# CH32X305RCT-R0.net
KiCad netlist of a schematic drawn in Altium Designer
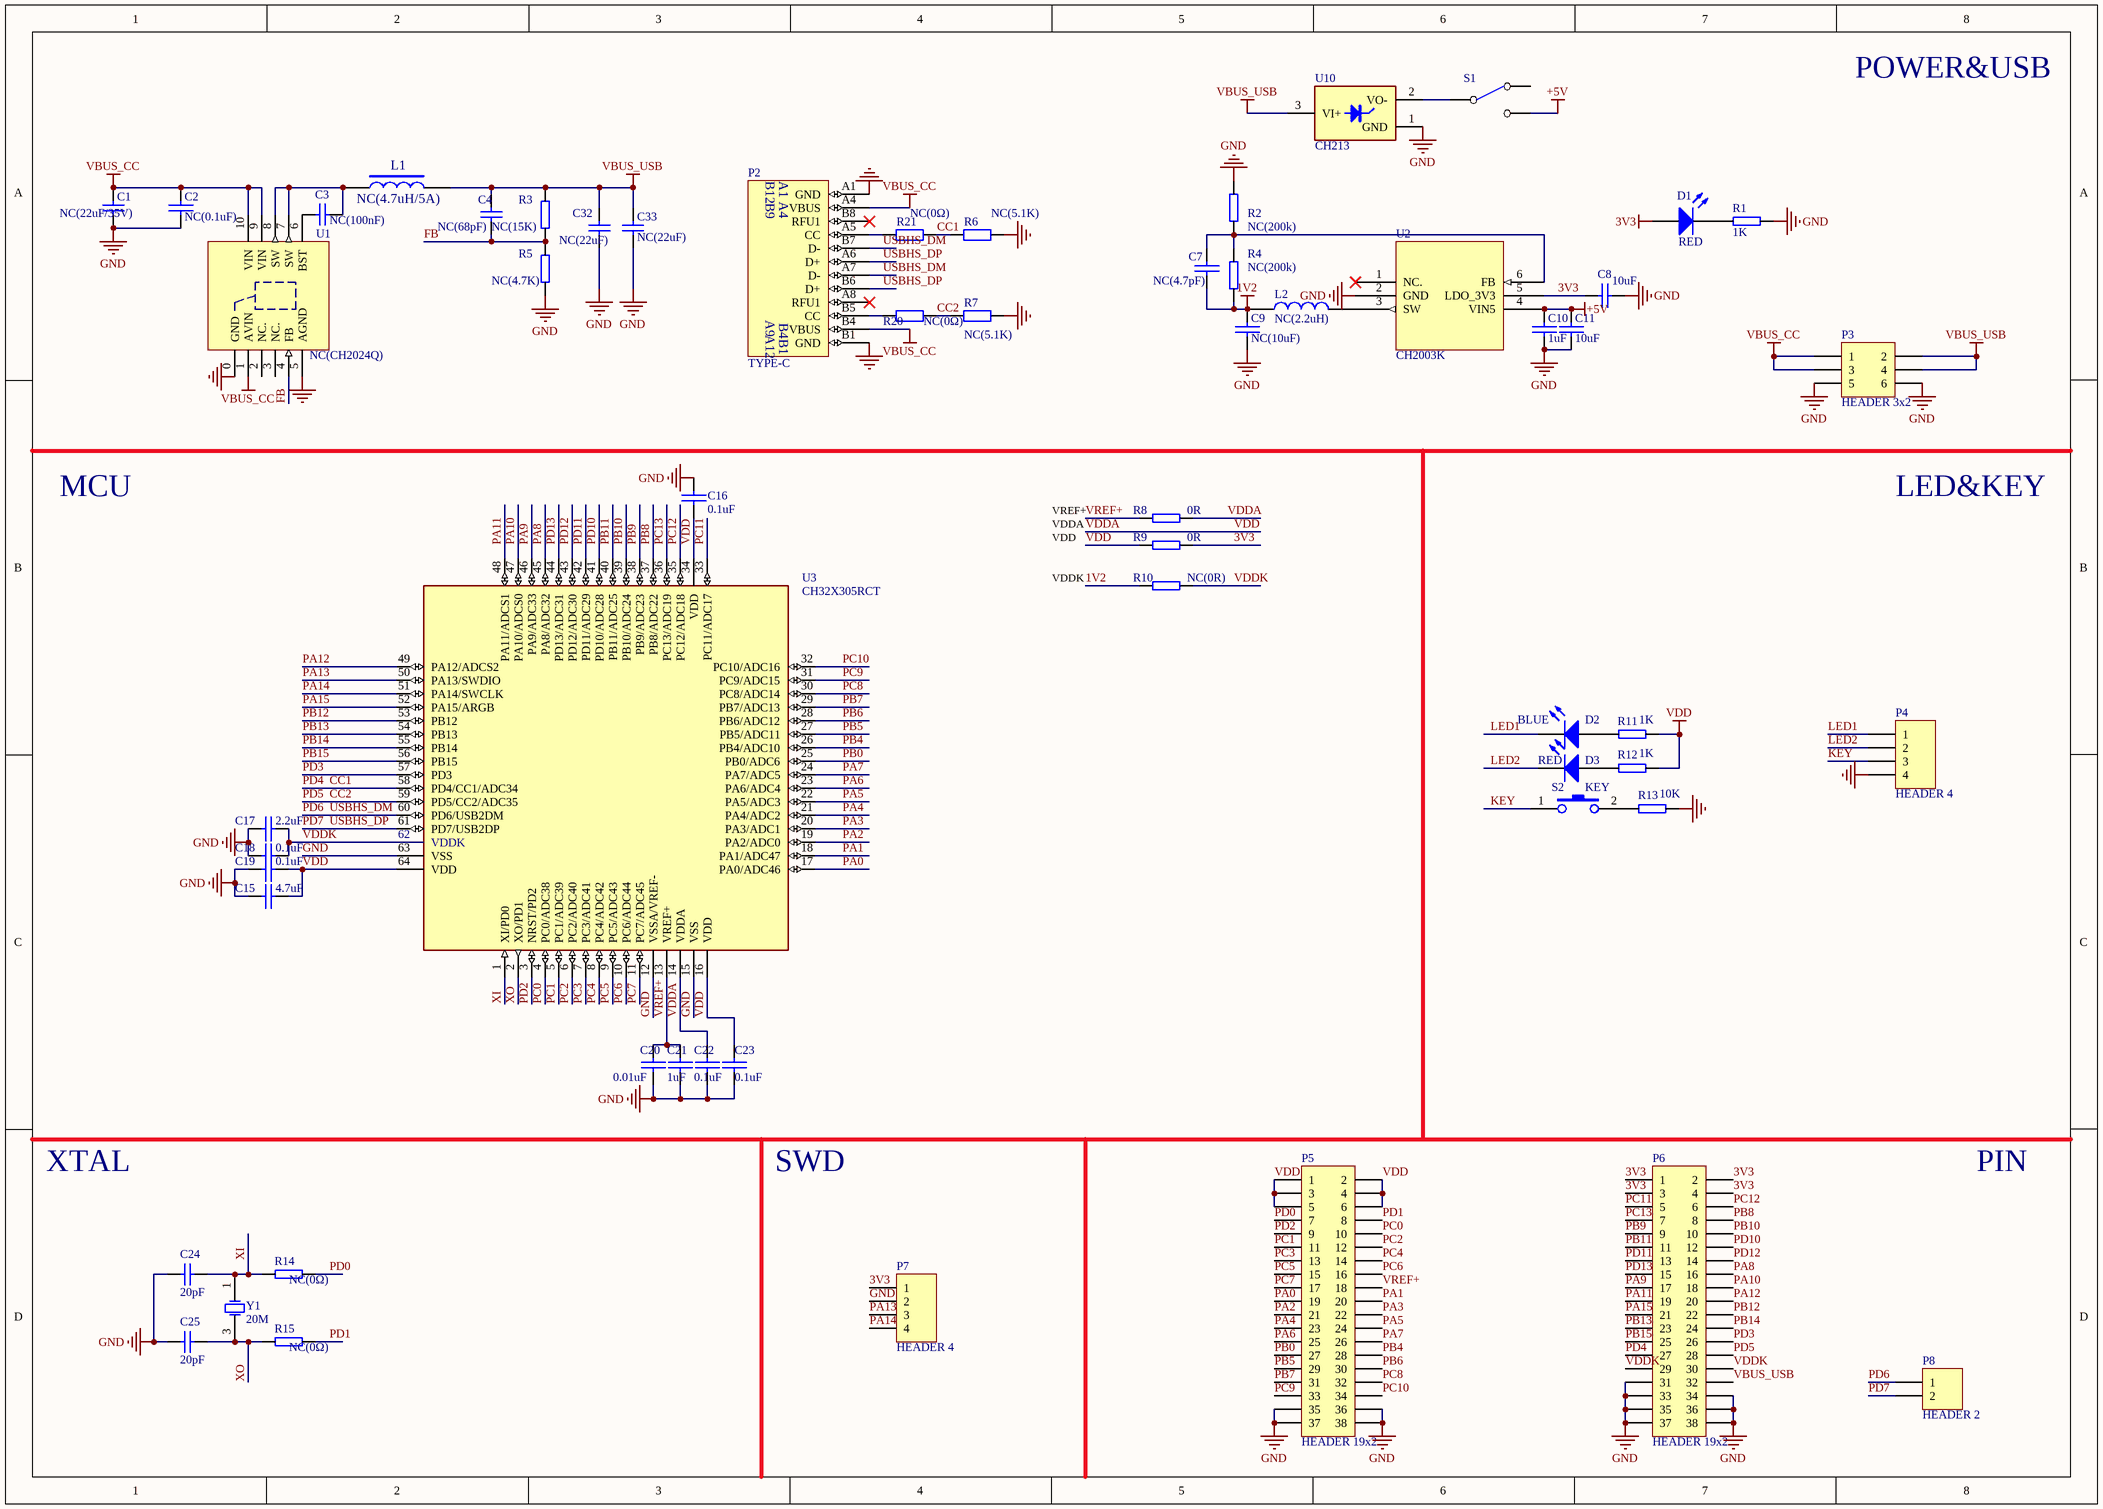
[diagram p0: CH32X305RCT-R0.SchDoc]

(export (version "E")
  (design (tool "Eeschema 10.0.6"))
  (components
    (comp (ref "C1")
      (value "NC(22uF/35V)")
      (footprint "0805_C")
      (description "贴片电容")
      (libsource (lib "Miscellaneous Devices LC") (part "0603 100nF (104) 10% 50V"))
    )
    (comp (ref "C2")
      (value "NC(0.1uF)")
      (footprint "0402_C")
      (description "Capacitor")
      (libsource (lib "") (part "CAP_1"))
    )
    (comp (ref "C3")
      (value "NC(100nF)")
      (footprint "0402_C")
      (description "贴片电容")
      (libsource (lib "Miscellaneous Devices LC") (part "0603 1uF (105) 10% 50V"))
    )
    (comp (ref "C4")
      (value "NC(68pF)")
      (footprint "0402_C")
      (description "贴片电容")
      (libsource (lib "Miscellaneous Devices LC") (part "0603 100nF (104) 10% 50V"))
    )
    (comp (ref "C7")
      (value "NC(4.7pF)")
      (footprint "0402_C")
      (description "Capacitor")
      (libsource (lib "*") (part "CAP"))
    )
    (comp (ref "C8")
      (value "10uF")
      (footprint "0603_C")
      (description "Capacitor")
      (libsource (lib "") (part "CAP_1"))
    )
    (comp (ref "C9")
      (value "NC(10uF)")
      (footprint "0603_C")
      (description "Capacitor")
      (libsource (lib "") (part "CAP_1"))
    )
    (comp (ref "C10")
      (value "1uF")
      (footprint "0402_C")
      (description "Capacitor")
      (libsource (lib "*") (part "CAP"))
    )
    (comp (ref "C11")
      (value "10uF")
      (footprint "0603_C")
      (description "Capacitor")
      (libsource (lib "") (part "CAP_1"))
    )
    (comp (ref "C15")
      (value "4.7uF")
      (footprint "0402_C")
      (description "Capacitor")
      (libsource (lib "*") (part "CAP"))
    )
    (comp (ref "C16")
      (value "0.1uF")
      (footprint "0402_C")
      (description "Capacitor")
      (libsource (lib "*") (part "CAP"))
    )
    (comp (ref "C17")
      (value "2.2uF")
      (footprint "0402_C")
      (description "Capacitor")
      (libsource (lib "*") (part "CAP"))
    )
    (comp (ref "C18")
      (value "0.1uF")
      (footprint "0402_C")
      (description "Capacitor")
      (libsource (lib "*") (part "CAP"))
    )
    (comp (ref "C19")
      (value "0.1uF")
      (footprint "0402_C")
      (description "Capacitor")
      (libsource (lib "*") (part "CAP"))
    )
    (comp (ref "C20")
      (value "0.01uF")
      (footprint "0402_C")
      (description "Capacitor")
      (libsource (lib "*") (part "CAP"))
    )
    (comp (ref "C21")
      (value "1uF")
      (footprint "0402_C")
      (description "Capacitor")
      (libsource (lib "*") (part "CAP"))
    )
    (comp (ref "C22")
      (value "0.1uF")
      (footprint "0402_C")
      (description "Capacitor")
      (libsource (lib "*") (part "CAP"))
    )
    (comp (ref "C23")
      (value "0.1uF")
      (footprint "0402_C")
      (description "Capacitor")
      (libsource (lib "*") (part "CAP"))
    )
    (comp (ref "C24")
      (value "20pF")
      (footprint "0402_C")
      (description "Capacitor")
      (libsource (lib "Miscellaneous Devices") (part "Cap"))
    )
    (comp (ref "C25")
      (value "20pF")
      (footprint "0402_C")
      (description "Capacitor")
      (libsource (lib "Miscellaneous Devices") (part "Cap"))
    )
    (comp (ref "C32")
      (value "NC(22uF)")
      (footprint "0805_C")
      (description "贴片电容")
      (libsource (lib "Miscellaneous Devices LC") (part "0603 100nF (104) 10% 50V"))
    )
    (comp (ref "C33")
      (value "NC(22uF)")
      (footprint "0805_C")
      (description "贴片电容")
      (libsource (lib "Miscellaneous Devices LC") (part "0603 100nF (104) 10% 50V"))
    )
    (comp (ref "D1")
      (value "RED")
      (footprint "0603+")
      (description "Typical INFRARED GaAs LED")
      (fields (field (name "PUBLISHER") "Altium Limited"))
      (libsource (lib "*") (part "LED0"))
    )
    (comp (ref "D2")
      (value "BLUE")
      (footprint "0603+")
      (description "Typical INFRARED GaAs LED")
      (fields (field (name "PUBLISHER") "Altium Limited"))
      (libsource (lib "*") (part "LED0"))
    )
    (comp (ref "D3")
      (value "RED")
      (footprint "0603+")
      (description "Typical INFRARED GaAs LED")
      (fields (field (name "PUBLISHER") "Altium Limited"))
      (libsource (lib "*") (part "LED0"))
    )
    (comp (ref "L1")
      (value "NC(4.7uH/5A)")
      (footprint "IND-SMD_L7.0-W6.6")
      (libsource (lib "wch_sch_others") (part "INDUCTOR"))
    )
    (comp (ref "L2") (value "NC(2.2uH)") (footprint "CD32") (libsource (lib "*") (part "INDUCTOR")))
    (comp (ref "P2")
      (value "TYPE-C")
      (footprint "TYPE-C-Receptacle-2.0")
      (libsource (lib "*") (part "TYPE-C1"))
    )
    (comp (ref "P3")
      (value "HEADER 3x2")
      (footprint "MYPCB:IDC6-2.54mm")
      (description "Header, 3-Pin, Dual row")
      (libsource (lib "wch_sch_others") (part "HEADER 3x2"))
    )
    (comp (ref "P4")
      (value "HEADER 4")
      (footprint "SIP4-2.54mm")
      (description "Header, 4-Pin")
      (libsource (lib "wch_sch_others") (part "HEADER 4"))
    )
    (comp (ref "P5")
      (value "HEADER 19x2")
      (footprint "MYPCB:IDC38-2.54MM")
      (description "Header, 19-Pin, Dual row")
      (libsource (lib "wch_sch_others") (part "HEADER 19x2"))
    )
    (comp (ref "P6")
      (value "HEADER 19x2")
      (footprint "MYPCB:IDC38-2.54MM")
      (description "Header, 19-Pin, Dual row")
      (libsource (lib "wch_sch_others") (part "HEADER 19x2"))
    )
    (comp (ref "P7")
      (value "HEADER 4")
      (footprint "SIP4-2.54mm")
      (description "Header, 4-Pin")
      (libsource (lib "wch_sch_others") (part "HEADER 4"))
    )
    (comp (ref "P8")
      (value "HEADER 2")
      (footprint "MYPCB:SIP2-2.54mm")
      (description "Header, 2-Pin")
      (libsource (lib "wch_sch_others") (part "HEADER 2"))
    )
    (comp (ref "R1") (value "1K") (footprint "0402") (libsource (lib "wch_sch_others") (part "RES")))
    (comp (ref "R2") (value "NC(200k)") (footprint "0402") (libsource (lib "") (part "RES_1")))
    (comp (ref "R3") (value "NC(15K)") (footprint "0402") (libsource (lib "wch_sch_others(1)") (part "RES")))
    (comp (ref "R4") (value "NC(200k)") (footprint "0402") (libsource (lib "") (part "RES_1")))
    (comp (ref "R5") (value "NC(4.7K)") (footprint "0402") (libsource (lib "wch_sch_others(1)") (part "RES")))
    (comp (ref "R6")
      (value "NC(5.1K)")
      (footprint "0402")
      (description "Resistor")
      (libsource (lib "Miscellaneous Devices") (part "Res2"))
    )
    (comp (ref "R7")
      (value "NC(5.1K)")
      (footprint "0402")
      (description "Resistor")
      (libsource (lib "Miscellaneous Devices") (part "Res2"))
    )
    (comp (ref "R8") (value "0R") (footprint "0402") (libsource (lib "*") (part "R")))
    (comp (ref "R9") (value "0R") (footprint "0402") (libsource (lib "*") (part "R")))
    (comp (ref "R10") (value "NC(0R)") (footprint "0402") (libsource (lib "*") (part "R")))
    (comp (ref "R11") (value "1K") (footprint "0402") (libsource (lib "wch_sch_others") (part "RES")))
    (comp (ref "R12") (value "1K") (footprint "0402") (libsource (lib "wch_sch_others") (part "RES")))
    (comp (ref "R13") (value "10K") (footprint "0402") (libsource (lib "wch_sch_others") (part "RES")))
    (comp (ref "R14") (value "NC(0Ω)") (footprint "0402") (libsource (lib "") (part "RES_1")))
    (comp (ref "R15") (value "NC(0Ω)") (footprint "0402") (libsource (lib "") (part "RES_1")))
    (comp (ref "R20")
      (value "NC(0Ω)")
      (footprint "0402")
      (description "Resistor")
      (libsource (lib "Miscellaneous Devices") (part "Res2"))
    )
    (comp (ref "R21")
      (value "NC(0Ω)")
      (footprint "0402")
      (description "Resistor")
      (libsource (lib "Miscellaneous Devices") (part "Res2"))
    )
    (comp (ref "S1") (value "SW SPDT") (footprint "SW1") (libsource (lib "*") (part "SW SPDT")))
    (comp (ref "S2")
      (value "KEY")
      (footprint "SMD_6.1x3.65x2.5mm-KEY")
      (libsource (lib "wch_sch_others") (part "KEY1"))
    )
    (comp (ref "U1")
      (value "NC(CH2024Q)")
      (footprint "DFN10_3X3")
      (description "Step-Down DC-DC Converter, 28V input, FB 1.2V, 3A output")
      (libsource (lib "DHXXXSCH") (part "CH2024Q"))
    )
    (comp (ref "U2")
      (value "CH2003K")
      (footprint "SOT-23-6")
      (description "Step-Down DC-DC Converter, 5V input, FB 0.6V, 800mA output, with LDO 3.3V * 200mA")
      (libsource (lib "DHXXXSCH") (part "CH2003K"))
    )
    (comp (ref "U3")
      (value "CH32X305RCT")
      (footprint "LQFP64_7X7")
      (description "RISC-V FPU MCU, 480MHz, USB2.0_480Mbps, PD, HSADC")
      (libsource (lib "DHXXXSCH") (part "CH32X305RCT"))
    )
    (comp (ref "U10")
      (value "CH213")
      (footprint "SOT-23-3")
      (description "Ideal Diode 5V*1A")
      (libsource (lib "CHXXX") (part "CH213E"))
    )
    (comp (ref "Y1")
      (value "20M")
      (footprint "XT3225")
      (description "Crystal Oscillator")
      (fields (field (name "PUBLISHER") "Altium Limited"))
      (libsource (lib "Miscellaneous Devices") (part "XTAL"))
    )
  )
  (nets
    (net (code "1") (name "+5V") (class "Default")
      (node (ref "C10") (pin "2") (pinfunction "2_2") (pintype "passive"))
      (node (ref "C11") (pin "2") (pinfunction "2_2") (pintype "passive"))
      (node (ref "S1") (pin "2") (pinfunction "NC_2") (pintype "passive"))
      (node (ref "U2") (pin "4") (pinfunction "VIN5_4") (pintype "power_in"))
    )
    (net (code "2") (name "/CC1") (class "Default")
      (node (ref "P6") (pin "27") (pinfunction "27_27") (pintype "passive"))
      (node (ref "R21") (pin "2") (pinfunction "2_2") (pintype "passive"))
      (node (ref "R6") (pin "1") (pinfunction "1_1") (pintype "passive"))
      (node (ref "U3") (pin "58") (pinfunction "PD4/CC1/ADC34_58") (pintype "bidirectional"))
    )
    (net (code "3") (name "/CC2") (class "Default")
      (node (ref "P6") (pin "28") (pinfunction "28_28") (pintype "passive"))
      (node (ref "R20") (pin "2") (pinfunction "2_2") (pintype "passive"))
      (node (ref "R7") (pin "1") (pinfunction "1_1") (pintype "passive"))
      (node (ref "U3") (pin "59") (pinfunction "PD5/CC2/ADC35_59") (pintype "bidirectional"))
    )
    (net (code "4") (name "/FB") (class "Default")
      (node (ref "C4") (pin "2") (pinfunction "2_2") (pintype "passive"))
      (node (ref "R3") (pin "1") (pintype "passive"))
      (node (ref "R5") (pin "2") (pintype "passive"))
      (node (ref "U1") (pin "4") (pinfunction "FB_4") (pintype "input"))
    )
    (net (code "5") (name "/KEY") (class "Default")
      (node (ref "P4") (pin "3") (pinfunction "3_3") (pintype "passive"))
      (node (ref "S2") (pin "1") (pinfunction "1_1") (pintype "passive"))
    )
    (net (code "6") (name "/LED1") (class "Default")
      (node (ref "D2") (pin "2") (pinfunction "K_2") (pintype "passive"))
      (node (ref "P4") (pin "1") (pinfunction "1_1") (pintype "passive"))
    )
    (net (code "7") (name "/LED2") (class "Default")
      (node (ref "D3") (pin "2") (pinfunction "K_2") (pintype "passive"))
      (node (ref "P4") (pin "2") (pinfunction "2_2") (pintype "passive"))
    )
    (net (code "8") (name "/PA0") (class "Default")
      (node (ref "P5") (pin "19") (pinfunction "19_19") (pintype "passive"))
      (node (ref "U3") (pin "17") (pinfunction "PA0/ADC46_17") (pintype "bidirectional"))
    )
    (net (code "9") (name "/PA1") (class "Default")
      (node (ref "P5") (pin "20") (pinfunction "20_20") (pintype "passive"))
      (node (ref "U3") (pin "18") (pinfunction "PA1/ADC47_18") (pintype "bidirectional"))
    )
    (net (code "10") (name "/PA2") (class "Default")
      (node (ref "P5") (pin "21") (pinfunction "21_21") (pintype "passive"))
      (node (ref "U3") (pin "19") (pinfunction "PA2/ADC0_19") (pintype "bidirectional"))
    )
    (net (code "11") (name "/PA3") (class "Default")
      (node (ref "P5") (pin "22") (pinfunction "22_22") (pintype "passive"))
      (node (ref "U3") (pin "20") (pinfunction "PA3/ADC1_20") (pintype "bidirectional"))
    )
    (net (code "12") (name "/PA4") (class "Default")
      (node (ref "P5") (pin "23") (pinfunction "23_23") (pintype "passive"))
      (node (ref "U3") (pin "21") (pinfunction "PA4/ADC2_21") (pintype "bidirectional"))
    )
    (net (code "13") (name "/PA5") (class "Default")
      (node (ref "P5") (pin "24") (pinfunction "24_24") (pintype "passive"))
      (node (ref "U3") (pin "22") (pinfunction "PA5/ADC3_22") (pintype "bidirectional"))
    )
    (net (code "14") (name "/PA6") (class "Default")
      (node (ref "P5") (pin "25") (pinfunction "25_25") (pintype "passive"))
      (node (ref "U3") (pin "23") (pinfunction "PA6/ADC4_23") (pintype "bidirectional"))
    )
    (net (code "15") (name "/PA7") (class "Default")
      (node (ref "P5") (pin "26") (pinfunction "26_26") (pintype "passive"))
      (node (ref "U3") (pin "24") (pinfunction "PA7/ADC5_24") (pintype "bidirectional"))
    )
    (net (code "16") (name "/PA8") (class "Default")
      (node (ref "P6") (pin "16") (pinfunction "16_16") (pintype "passive"))
      (node (ref "U3") (pin "45") (pinfunction "PA8/ADC32_45") (pintype "bidirectional"))
    )
    (net (code "17") (name "/PA9") (class "Default")
      (node (ref "P6") (pin "17") (pinfunction "17_17") (pintype "passive"))
      (node (ref "U3") (pin "46") (pinfunction "PA9/ADC33_46") (pintype "bidirectional"))
    )
    (net (code "18") (name "/PA10") (class "Default")
      (node (ref "P6") (pin "18") (pinfunction "18_18") (pintype "passive"))
      (node (ref "U3") (pin "47") (pinfunction "PA10/ADCS0_47") (pintype "bidirectional"))
    )
    (net (code "19") (name "/PA11") (class "Default")
      (node (ref "P6") (pin "19") (pinfunction "19_19") (pintype "passive"))
      (node (ref "U3") (pin "48") (pinfunction "PA11/ADCS1_48") (pintype "bidirectional"))
    )
    (net (code "20") (name "/PA12") (class "Default")
      (node (ref "P6") (pin "20") (pinfunction "20_20") (pintype "passive"))
      (node (ref "U3") (pin "49") (pinfunction "PA12/ADCS2_49") (pintype "bidirectional"))
    )
    (net (code "21") (name "/PA13") (class "Default")
      (node (ref "P7") (pin "3") (pinfunction "3_3") (pintype "passive"))
      (node (ref "U3") (pin "50") (pinfunction "PA13/SWDIO_50") (pintype "bidirectional"))
    )
    (net (code "22") (name "/PA14") (class "Default")
      (node (ref "P7") (pin "4") (pinfunction "4_4") (pintype "passive"))
      (node (ref "U3") (pin "51") (pinfunction "PA14/SWCLK_51") (pintype "bidirectional"))
    )
    (net (code "23") (name "/PA15") (class "Default")
      (node (ref "P6") (pin "21") (pinfunction "21_21") (pintype "passive"))
      (node (ref "U3") (pin "52") (pinfunction "PA15/ARGB_52") (pintype "bidirectional"))
    )
    (net (code "24") (name "/PB0") (class "Default")
      (node (ref "P5") (pin "27") (pinfunction "27_27") (pintype "passive"))
      (node (ref "U3") (pin "25") (pinfunction "PB0/ADC6_25") (pintype "bidirectional"))
    )
    (net (code "25") (name "/PB4") (class "Default")
      (node (ref "P5") (pin "28") (pinfunction "28_28") (pintype "passive"))
      (node (ref "U3") (pin "26") (pinfunction "PB4/ADC10_26") (pintype "bidirectional"))
    )
    (net (code "26") (name "/PB5") (class "Default")
      (node (ref "P5") (pin "29") (pinfunction "29_29") (pintype "passive"))
      (node (ref "U3") (pin "27") (pinfunction "PB5/ADC11_27") (pintype "bidirectional"))
    )
    (net (code "27") (name "/PB6") (class "Default")
      (node (ref "P5") (pin "30") (pinfunction "30_30") (pintype "passive"))
      (node (ref "U3") (pin "28") (pinfunction "PB6/ADC12_28") (pintype "bidirectional"))
    )
    (net (code "28") (name "/PB7") (class "Default")
      (node (ref "P5") (pin "31") (pinfunction "31_31") (pintype "passive"))
      (node (ref "U3") (pin "29") (pinfunction "PB7/ADC13_29") (pintype "bidirectional"))
    )
    (net (code "29") (name "/PB8") (class "Default")
      (node (ref "P6") (pin "8") (pinfunction "8_8") (pintype "passive"))
      (node (ref "U3") (pin "37") (pinfunction "PB8/ADC22_37") (pintype "bidirectional"))
    )
    (net (code "30") (name "/PB9") (class "Default")
      (node (ref "P6") (pin "9") (pinfunction "9_9") (pintype "passive"))
      (node (ref "U3") (pin "38") (pinfunction "PB9/ADC23_38") (pintype "bidirectional"))
    )
    (net (code "31") (name "/PB10") (class "Default")
      (node (ref "P6") (pin "10") (pinfunction "10_10") (pintype "passive"))
      (node (ref "U3") (pin "39") (pinfunction "PB10/ADC24_39") (pintype "bidirectional"))
    )
    (net (code "32") (name "/PB11") (class "Default")
      (node (ref "P6") (pin "11") (pinfunction "11_11") (pintype "passive"))
      (node (ref "U3") (pin "40") (pinfunction "PB11/ADC25_40") (pintype "bidirectional"))
    )
    (net (code "33") (name "/PB12") (class "Default")
      (node (ref "P6") (pin "22") (pinfunction "22_22") (pintype "passive"))
      (node (ref "U3") (pin "53") (pinfunction "PB12_53") (pintype "bidirectional"))
    )
    (net (code "34") (name "/PB13") (class "Default")
      (node (ref "P6") (pin "23") (pinfunction "23_23") (pintype "passive"))
      (node (ref "U3") (pin "54") (pinfunction "PB13_54") (pintype "bidirectional"))
    )
    (net (code "35") (name "/PB14") (class "Default")
      (node (ref "P6") (pin "24") (pinfunction "24_24") (pintype "passive"))
      (node (ref "U3") (pin "55") (pinfunction "PB14_55") (pintype "bidirectional"))
    )
    (net (code "36") (name "/PB15") (class "Default")
      (node (ref "P6") (pin "25") (pinfunction "25_25") (pintype "passive"))
      (node (ref "U3") (pin "56") (pinfunction "PB15_56") (pintype "bidirectional"))
    )
    (net (code "37") (name "/PC0") (class "Default")
      (node (ref "P5") (pin "10") (pinfunction "10_10") (pintype "passive"))
      (node (ref "U3") (pin "4") (pinfunction "PC0/ADC38_4") (pintype "bidirectional"))
    )
    (net (code "38") (name "/PC1") (class "Default")
      (node (ref "P5") (pin "11") (pinfunction "11_11") (pintype "passive"))
      (node (ref "U3") (pin "5") (pinfunction "PC1/ADC39_5") (pintype "bidirectional"))
    )
    (net (code "39") (name "/PC2") (class "Default")
      (node (ref "P5") (pin "12") (pinfunction "12_12") (pintype "passive"))
      (node (ref "U3") (pin "6") (pinfunction "PC2/ADC40_6") (pintype "bidirectional"))
    )
    (net (code "40") (name "/PC3") (class "Default")
      (node (ref "P5") (pin "13") (pinfunction "13_13") (pintype "passive"))
      (node (ref "U3") (pin "7") (pinfunction "PC3/ADC41_7") (pintype "bidirectional"))
    )
    (net (code "41") (name "/PC4") (class "Default")
      (node (ref "P5") (pin "14") (pinfunction "14_14") (pintype "passive"))
      (node (ref "U3") (pin "8") (pinfunction "PC4/ADC42_8") (pintype "bidirectional"))
    )
    (net (code "42") (name "/PC5") (class "Default")
      (node (ref "P5") (pin "15") (pinfunction "15_15") (pintype "passive"))
      (node (ref "U3") (pin "9") (pinfunction "PC5/ADC43_9") (pintype "bidirectional"))
    )
    (net (code "43") (name "/PC6") (class "Default")
      (node (ref "P5") (pin "16") (pinfunction "16_16") (pintype "passive"))
      (node (ref "U3") (pin "10") (pinfunction "PC6/ADC44_10") (pintype "bidirectional"))
    )
    (net (code "44") (name "/PC7") (class "Default")
      (node (ref "P5") (pin "17") (pinfunction "17_17") (pintype "passive"))
      (node (ref "U3") (pin "11") (pinfunction "PC7/ADC45_11") (pintype "bidirectional"))
    )
    (net (code "45") (name "/PC8") (class "Default")
      (node (ref "P5") (pin "32") (pinfunction "32_32") (pintype "passive"))
      (node (ref "U3") (pin "30") (pinfunction "PC8/ADC14_30") (pintype "bidirectional"))
    )
    (net (code "46") (name "/PC9") (class "Default")
      (node (ref "P5") (pin "33") (pinfunction "33_33") (pintype "passive"))
      (node (ref "U3") (pin "31") (pinfunction "PC9/ADC15_31") (pintype "bidirectional"))
    )
    (net (code "47") (name "/PC10") (class "Default")
      (node (ref "P5") (pin "34") (pinfunction "34_34") (pintype "passive"))
      (node (ref "U3") (pin "32") (pinfunction "PC10/ADC16_32") (pintype "bidirectional"))
    )
    (net (code "48") (name "/PC11") (class "Default")
      (node (ref "P6") (pin "5") (pinfunction "5_5") (pintype "passive"))
      (node (ref "U3") (pin "33") (pinfunction "PC11/ADC17_33") (pintype "bidirectional"))
    )
    (net (code "49") (name "/PC12") (class "Default")
      (node (ref "P6") (pin "6") (pinfunction "6_6") (pintype "passive"))
      (node (ref "U3") (pin "35") (pinfunction "PC12/ADC18_35") (pintype "bidirectional"))
    )
    (net (code "50") (name "/PC13") (class "Default")
      (node (ref "P6") (pin "7") (pinfunction "7_7") (pintype "passive"))
      (node (ref "U3") (pin "36") (pinfunction "PC13/ADC19_36") (pintype "bidirectional"))
    )
    (net (code "51") (name "/PD0") (class "Default")
      (node (ref "P5") (pin "7") (pinfunction "7_7") (pintype "passive"))
      (node (ref "R14") (pin "1") (pintype "passive"))
    )
    (net (code "52") (name "/PD1") (class "Default")
      (node (ref "P5") (pin "8") (pinfunction "8_8") (pintype "passive"))
      (node (ref "R15") (pin "1") (pintype "passive"))
    )
    (net (code "53") (name "/PD2") (class "Default")
      (node (ref "P5") (pin "9") (pinfunction "9_9") (pintype "passive"))
      (node (ref "U3") (pin "3") (pinfunction "NRST/PD2_3") (pintype "bidirectional"))
    )
    (net (code "54") (name "/PD3") (class "Default")
      (node (ref "P6") (pin "26") (pinfunction "26_26") (pintype "passive"))
      (node (ref "U3") (pin "57") (pinfunction "PD3_57") (pintype "bidirectional"))
    )
    (net (code "55") (name "/PD6") (class "Default")
      (node (ref "P2") (pin "A7") (pinfunction "D-_A7") (pintype "bidirectional"))
      (node (ref "P2") (pin "B7") (pinfunction "D-_B7") (pintype "bidirectional"))
      (node (ref "P8") (pin "1") (pinfunction "1_1") (pintype "passive"))
      (node (ref "U3") (pin "60") (pinfunction "PD6/USB2DM_60") (pintype "bidirectional"))
    )
    (net (code "56") (name "/PD7") (class "Default")
      (node (ref "P2") (pin "A6") (pinfunction "D+_A6") (pintype "bidirectional"))
      (node (ref "P2") (pin "B6") (pinfunction "D+_B6") (pintype "bidirectional"))
      (node (ref "P8") (pin "2") (pinfunction "2_2") (pintype "passive"))
      (node (ref "U3") (pin "61") (pinfunction "PD7/USB2DP_61") (pintype "bidirectional"))
    )
    (net (code "57") (name "/PD10") (class "Default")
      (node (ref "P6") (pin "12") (pinfunction "12_12") (pintype "passive"))
      (node (ref "U3") (pin "41") (pinfunction "PD10/ADC28_41") (pintype "bidirectional"))
    )
    (net (code "58") (name "/PD11") (class "Default")
      (node (ref "P6") (pin "13") (pinfunction "13_13") (pintype "passive"))
      (node (ref "U3") (pin "42") (pinfunction "PD11/ADC29_42") (pintype "bidirectional"))
    )
    (net (code "59") (name "/PD12") (class "Default")
      (node (ref "P6") (pin "14") (pinfunction "14_14") (pintype "passive"))
      (node (ref "U3") (pin "43") (pinfunction "PD12/ADC30_43") (pintype "bidirectional"))
    )
    (net (code "60") (name "/PD13") (class "Default")
      (node (ref "P6") (pin "15") (pinfunction "15_15") (pintype "passive"))
      (node (ref "U3") (pin "44") (pinfunction "PD13/ADC31_44") (pintype "bidirectional"))
    )
    (net (code "61") (name "/VDDK") (class "Default")
      (node (ref "C17") (pin "1") (pinfunction "1_1") (pintype "passive"))
      (node (ref "C18") (pin "1") (pinfunction "1_1") (pintype "passive"))
      (node (ref "P6") (pin "29") (pinfunction "29_29") (pintype "passive"))
      (node (ref "P6") (pin "30") (pinfunction "30_30") (pintype "passive"))
      (node (ref "R10") (pin "1") (pinfunction "1_1") (pintype "passive"))
      (node (ref "U3") (pin "62") (pinfunction "VDDK_62") (pintype "power_in"))
    )
    (net (code "62") (name "/VREF+") (class "Default")
      (node (ref "C20") (pin "1") (pinfunction "1_1") (pintype "passive"))
      (node (ref "C21") (pin "1") (pinfunction "1_1") (pintype "passive"))
      (node (ref "P5") (pin "18") (pinfunction "18_18") (pintype "passive"))
      (node (ref "R8") (pin "2") (pinfunction "2_2") (pintype "passive"))
      (node (ref "U3") (pin "13") (pinfunction "VREF+_13") (pintype "power_in"))
    )
    (net (code "63") (name "/XI") (class "Default")
      (node (ref "C24") (pin "1") (pinfunction "1_1") (pintype "passive"))
      (node (ref "R14") (pin "2") (pintype "passive"))
      (node (ref "U3") (pin "1") (pinfunction "XI/PD0_1") (pintype "input"))
      (node (ref "Y1") (pin "1") (pinfunction "OSC1_1") (pintype "passive"))
    )
    (net (code "64") (name "/XO") (class "Default")
      (node (ref "C25") (pin "1") (pinfunction "1_1") (pintype "passive"))
      (node (ref "R15") (pin "2") (pintype "passive"))
      (node (ref "U3") (pin "2") (pinfunction "XO/PD1_2") (pintype "output"))
      (node (ref "Y1") (pin "3") (pinfunction "OSC2_3") (pintype "passive"))
    )
    (net (code "65") (name "1V2") (class "Default")
      (node (ref "C7") (pin "1") (pinfunction "1_1") (pintype "passive"))
      (node (ref "C9") (pin "2") (pinfunction "2_2") (pintype "passive"))
      (node (ref "L2") (pin "2") (pinfunction "2_2") (pintype "passive"))
      (node (ref "R10") (pin "2") (pinfunction "2_2") (pintype "passive"))
      (node (ref "R4") (pin "1") (pintype "passive"))
    )
    (net (code "66") (name "3V3") (class "Default")
      (node (ref "C8") (pin "2") (pinfunction "2_2") (pintype "passive"))
      (node (ref "D1") (pin "1") (pinfunction "A_1") (pintype "passive"))
      (node (ref "P6") (pin "1") (pinfunction "1_1") (pintype "passive"))
      (node (ref "P6") (pin "2") (pinfunction "2_2") (pintype "passive"))
      (node (ref "P6") (pin "3") (pinfunction "3_3") (pintype "passive"))
      (node (ref "P6") (pin "4") (pinfunction "4_4") (pintype "passive"))
      (node (ref "P7") (pin "1") (pinfunction "1_1") (pintype "passive"))
      (node (ref "R9") (pin "1") (pinfunction "1_1") (pintype "passive"))
      (node (ref "U2") (pin "5") (pinfunction "LDO_3V3_5") (pintype "power_in"))
    )
    (net (code "67") (name "GND") (class "Default")
      (node (ref "C1") (pin "1") (pinfunction "1_1") (pintype "passive"))
      (node (ref "C10") (pin "1") (pinfunction "1_1") (pintype "passive"))
      (node (ref "C11") (pin "1") (pinfunction "1_1") (pintype "passive"))
      (node (ref "C15") (pin "1") (pinfunction "1_1") (pintype "passive"))
      (node (ref "C16") (pin "1") (pinfunction "1_1") (pintype "passive"))
      (node (ref "C17") (pin "2") (pinfunction "2_2") (pintype "passive"))
      (node (ref "C18") (pin "2") (pinfunction "2_2") (pintype "passive"))
      (node (ref "C19") (pin "2") (pinfunction "2_2") (pintype "passive"))
      (node (ref "C2") (pin "1") (pinfunction "1_1") (pintype "passive"))
      (node (ref "C20") (pin "2") (pinfunction "2_2") (pintype "passive"))
      (node (ref "C21") (pin "2") (pinfunction "2_2") (pintype "passive"))
      (node (ref "C22") (pin "2") (pinfunction "2_2") (pintype "passive"))
      (node (ref "C23") (pin "2") (pinfunction "2_2") (pintype "passive"))
      (node (ref "C24") (pin "2") (pinfunction "2_2") (pintype "passive"))
      (node (ref "C25") (pin "2") (pinfunction "2_2") (pintype "passive"))
      (node (ref "C32") (pin "1") (pinfunction "1_1") (pintype "passive"))
      (node (ref "C33") (pin "1") (pinfunction "1_1") (pintype "passive"))
      (node (ref "C8") (pin "1") (pinfunction "1_1") (pintype "passive"))
      (node (ref "C9") (pin "1") (pinfunction "1_1") (pintype "passive"))
      (node (ref "P2") (pin "A1") (pinfunction "GND_A1") (pintype "bidirectional"))
      (node (ref "P2") (pin "B1") (pinfunction "GND_B1") (pintype "bidirectional"))
      (node (ref "P3") (pin "5") (pinfunction "5_5") (pintype "passive"))
      (node (ref "P3") (pin "6") (pinfunction "6_6") (pintype "passive"))
      (node (ref "P4") (pin "4") (pinfunction "4_4") (pintype "passive"))
      (node (ref "P5") (pin "35") (pinfunction "35_35") (pintype "passive"))
      (node (ref "P5") (pin "36") (pinfunction "36_36") (pintype "passive"))
      (node (ref "P5") (pin "37") (pinfunction "37_37") (pintype "passive"))
      (node (ref "P5") (pin "38") (pinfunction "38_38") (pintype "passive"))
      (node (ref "P6") (pin "31") (pinfunction "31_31") (pintype "passive"))
      (node (ref "P6") (pin "33") (pinfunction "33_33") (pintype "passive"))
      (node (ref "P6") (pin "34") (pinfunction "34_34") (pintype "passive"))
      (node (ref "P6") (pin "35") (pinfunction "35_35") (pintype "passive"))
      (node (ref "P6") (pin "36") (pinfunction "36_36") (pintype "passive"))
      (node (ref "P6") (pin "37") (pinfunction "37_37") (pintype "passive"))
      (node (ref "P6") (pin "38") (pinfunction "38_38") (pintype "passive"))
      (node (ref "P7") (pin "2") (pinfunction "2_2") (pintype "passive"))
      (node (ref "R1") (pin "2") (pintype "passive"))
      (node (ref "R13") (pin "1") (pintype "passive"))
      (node (ref "R2") (pin "2") (pintype "passive"))
      (node (ref "R5") (pin "1") (pintype "passive"))
      (node (ref "R6") (pin "2") (pinfunction "2_2") (pintype "passive"))
      (node (ref "R7") (pin "2") (pinfunction "2_2") (pintype "passive"))
      (node (ref "U1") (pin "0") (pinfunction "GND_0") (pintype "power_in"))
      (node (ref "U1") (pin "5") (pinfunction "AGND_5") (pintype "power_in"))
      (node (ref "U10") (pin "1") (pinfunction "GND_1") (pintype "power_in"))
      (node (ref "U2") (pin "2") (pinfunction "GND_2") (pintype "power_in"))
      (node (ref "U3") (pin "12") (pinfunction "VSSA/VREF-_12") (pintype "power_in"))
      (node (ref "U3") (pin "15") (pinfunction "VSS_15") (pintype "power_in"))
      (node (ref "U3") (pin "63") (pinfunction "VSS_63") (pintype "power_in"))
    )
    (net (code "68") (name "Net-(C3-Pad2)") (class "Default")
      (node (ref "C3") (pin "2") (pinfunction "2_2") (pintype "passive"))
      (node (ref "L1") (pin "1") (pinfunction "1_1") (pintype "passive"))
      (node (ref "U1") (pin "7") (pinfunction "SW_7") (pintype "output"))
      (node (ref "U1") (pin "8") (pinfunction "SW_8") (pintype "output"))
    )
    (net (code "69") (name "Net-(D1-K)") (class "Default")
      (node (ref "D1") (pin "2") (pinfunction "K_2") (pintype "passive"))
      (node (ref "R1") (pin "1") (pintype "passive"))
    )
    (net (code "70") (name "Net-(D2-A)") (class "Default")
      (node (ref "D2") (pin "1") (pinfunction "A_1") (pintype "passive"))
      (node (ref "R11") (pin "2") (pintype "passive"))
    )
    (net (code "71") (name "Net-(D3-A)") (class "Default")
      (node (ref "D3") (pin "1") (pinfunction "A_1") (pintype "passive"))
      (node (ref "R12") (pin "2") (pintype "passive"))
    )
    (net (code "72") (name "Net-(P2-CC-PadA5)") (class "Default")
      (node (ref "P2") (pin "A5") (pinfunction "CC_A5") (pintype "bidirectional"))
      (node (ref "R21") (pin "1") (pinfunction "1_1") (pintype "passive"))
    )
    (net (code "73") (name "Net-(P2-CC-PadB5)") (class "Default")
      (node (ref "P2") (pin "B5") (pinfunction "CC_B5") (pintype "bidirectional"))
      (node (ref "R20") (pin "1") (pinfunction "1_1") (pintype "passive"))
    )
    (net (code "74") (name "Net-(R13-Pad2)") (class "Default")
      (node (ref "R13") (pin "2") (pintype "passive"))
      (node (ref "S2") (pin "2") (pinfunction "2_2") (pintype "passive"))
    )
    (net (code "75") (name "Net-(S1-COMMON)") (class "Default")
      (node (ref "S1") (pin "1") (pinfunction "COMMON_1") (pintype "passive"))
      (node (ref "U10") (pin "2") (pinfunction "VO-_2") (pintype "power_in"))
    )
    (net (code "76") (name "Net-(U1-BST)") (class "Default")
      (node (ref "C3") (pin "1") (pinfunction "1_1") (pintype "passive"))
      (node (ref "U1") (pin "6") (pinfunction "BST_6") (pintype "power_in"))
    )
    (net (code "77") (name "Net-(U2-FB)") (class "Default")
      (node (ref "C7") (pin "2") (pinfunction "2_2") (pintype "passive"))
      (node (ref "R2") (pin "1") (pintype "passive"))
      (node (ref "R4") (pin "2") (pintype "passive"))
      (node (ref "U2") (pin "6") (pinfunction "FB_6") (pintype "input"))
    )
    (net (code "78") (name "Net-(U2-SW)") (class "Default")
      (node (ref "L2") (pin "1") (pinfunction "1_1") (pintype "passive"))
      (node (ref "U2") (pin "3") (pinfunction "SW_3") (pintype "output"))
    )
    (net (code "79") (name "VBUS_CC") (class "Default")
      (node (ref "C1") (pin "2") (pinfunction "2_2") (pintype "passive"))
      (node (ref "C2") (pin "2") (pinfunction "2_2") (pintype "passive"))
      (node (ref "P2") (pin "A4") (pinfunction "VBUS_A4") (pintype "bidirectional"))
      (node (ref "P2") (pin "B4") (pinfunction "VBUS_B4") (pintype "bidirectional"))
      (node (ref "P3") (pin "1") (pinfunction "1_1") (pintype "passive"))
      (node (ref "P3") (pin "3") (pinfunction "3_3") (pintype "passive"))
      (node (ref "U1") (pin "1") (pinfunction "AVIN_1") (pintype "power_in"))
      (node (ref "U1") (pin "10") (pinfunction "VIN_10") (pintype "power_in"))
      (node (ref "U1") (pin "9") (pinfunction "VIN_9") (pintype "power_in"))
    )
    (net (code "80") (name "VBUS_USB") (class "Default")
      (node (ref "C32") (pin "2") (pinfunction "2_2") (pintype "passive"))
      (node (ref "C33") (pin "2") (pinfunction "2_2") (pintype "passive"))
      (node (ref "C4") (pin "1") (pinfunction "1_1") (pintype "passive"))
      (node (ref "L1") (pin "2") (pinfunction "2_2") (pintype "passive"))
      (node (ref "P3") (pin "2") (pinfunction "2_2") (pintype "passive"))
      (node (ref "P3") (pin "4") (pinfunction "4_4") (pintype "passive"))
      (node (ref "P6") (pin "32") (pinfunction "32_32") (pintype "passive"))
      (node (ref "R3") (pin "2") (pintype "passive"))
      (node (ref "U10") (pin "3") (pinfunction "VI+_3") (pintype "power_in"))
    )
    (net (code "81") (name "VDD") (class "Default")
      (node (ref "C15") (pin "2") (pinfunction "2_2") (pintype "passive"))
      (node (ref "C16") (pin "2") (pinfunction "2_2") (pintype "passive"))
      (node (ref "C19") (pin "1") (pinfunction "1_1") (pintype "passive"))
      (node (ref "C22") (pin "1") (pinfunction "1_1") (pintype "passive"))
      (node (ref "C23") (pin "1") (pinfunction "1_1") (pintype "passive"))
      (node (ref "P5") (pin "1") (pinfunction "1_1") (pintype "passive"))
      (node (ref "P5") (pin "2") (pinfunction "2_2") (pintype "passive"))
      (node (ref "P5") (pin "3") (pinfunction "3_3") (pintype "passive"))
      (node (ref "P5") (pin "4") (pinfunction "4_4") (pintype "passive"))
      (node (ref "P5") (pin "5") (pinfunction "5_5") (pintype "passive"))
      (node (ref "P5") (pin "6") (pinfunction "6_6") (pintype "passive"))
      (node (ref "R11") (pin "1") (pintype "passive"))
      (node (ref "R12") (pin "1") (pintype "passive"))
      (node (ref "R8") (pin "1") (pinfunction "1_1") (pintype "passive"))
      (node (ref "R9") (pin "2") (pinfunction "2_2") (pintype "passive"))
      (node (ref "U3") (pin "14") (pinfunction "VDDA_14") (pintype "power_in"))
      (node (ref "U3") (pin "16") (pinfunction "VDD_16") (pintype "power_in"))
      (node (ref "U3") (pin "34") (pinfunction "VDD_34") (pintype "power_in"))
      (node (ref "U3") (pin "64") (pinfunction "VDD_64") (pintype "power_in"))
    )
    (net (code "82") (name "unconnected-(P2-RFU1-PadA8)") (class "Default")
      (node (ref "P2") (pin "A8") (pinfunction "RFU1_A8") (pintype "bidirectional+no_connect"))
    )
    (net (code "83") (name "unconnected-(P2-RFU1-PadB8)") (class "Default")
      (node (ref "P2") (pin "B8") (pinfunction "RFU1_B8") (pintype "bidirectional+no_connect"))
    )
    (net (code "84") (name "unconnected-(S1-NO-Pad3)") (class "Default")
      (node (ref "S1") (pin "3") (pinfunction "NO_3") (pintype "passive"))
    )
    (net (code "85") (name "unconnected-(U1-NC.-Pad2)") (class "Default")
      (node (ref "U1") (pin "2") (pinfunction "NC._2") (pintype "passive"))
    )
    (net (code "86") (name "unconnected-(U1-NC.-Pad3)") (class "Default")
      (node (ref "U1") (pin "3") (pinfunction "NC._3") (pintype "passive"))
    )
    (net (code "87") (name "unconnected-(U2-NC.-Pad1)") (class "Default")
      (node (ref "U2") (pin "1") (pinfunction "NC._1") (pintype "passive+no_connect"))
    )
  )
)
